# OurEDA-P1K_cam.net
KiCad netlist of a schematic drawn in Altium Designer
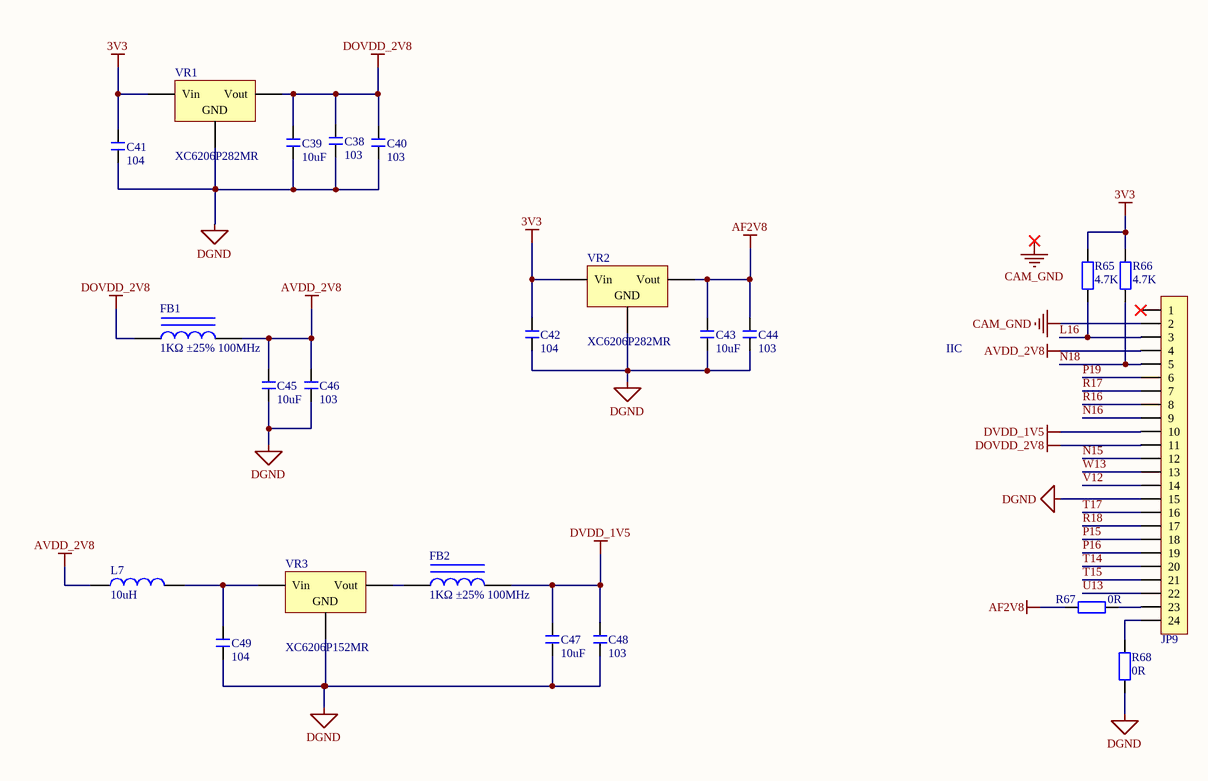
[diagram p0: OurEDA-P1K_cam.SchDoc]

(export (version "E")
  (design (tool "Eeschema 10.0.6"))
  (components
    (comp (ref "C38")
      (value "103")
      (footprint "C 0603_L")
      (description "无极性贴片电容")
      (fields (field (name "版权归属") "源创客"))
      (libsource (lib "3.1   - 电阻-电容-电感") (part "C"))
    )
    (comp (ref "C39")
      (value "10uF")
      (footprint "C 0603_L")
      (description "无极性贴片电容")
      (fields (field (name "版权归属") "源创客"))
      (libsource (lib "3.1   - 电阻-电容-电感") (part "C"))
    )
    (comp (ref "C40")
      (value "103")
      (footprint "C 0603_L")
      (description "无极性贴片电容")
      (fields (field (name "版权归属") "源创客"))
      (libsource (lib "3.1   - 电阻-电容-电感") (part "C"))
    )
    (comp (ref "C41")
      (value "104")
      (footprint "C 0603_L")
      (description "无极性贴片电容")
      (fields (field (name "版权归属") "源创客"))
      (libsource (lib "3.1   - 电阻-电容-电感") (part "C"))
    )
    (comp (ref "C42")
      (value "104")
      (footprint "C 0603_L")
      (description "无极性贴片电容")
      (fields (field (name "版权归属") "源创客"))
      (libsource (lib "3.1   - 电阻-电容-电感") (part "C"))
    )
    (comp (ref "C43")
      (value "10uF")
      (footprint "C 0603_L")
      (description "无极性贴片电容")
      (fields (field (name "版权归属") "源创客"))
      (libsource (lib "3.1   - 电阻-电容-电感") (part "C"))
    )
    (comp (ref "C44")
      (value "103")
      (footprint "C 0603_L")
      (description "无极性贴片电容")
      (fields (field (name "版权归属") "源创客"))
      (libsource (lib "3.1   - 电阻-电容-电感") (part "C"))
    )
    (comp (ref "C45")
      (value "10uF")
      (footprint "C 0603_L")
      (description "无极性贴片电容")
      (fields (field (name "版权归属") "源创客"))
      (libsource (lib "3.1   - 电阻-电容-电感") (part "C"))
    )
    (comp (ref "C46")
      (value "103")
      (footprint "C 0603_L")
      (description "无极性贴片电容")
      (fields (field (name "版权归属") "源创客"))
      (libsource (lib "3.1   - 电阻-电容-电感") (part "C"))
    )
    (comp (ref "C47")
      (value "10uF")
      (footprint "C 0603_L")
      (description "无极性贴片电容")
      (fields (field (name "版权归属") "源创客"))
      (libsource (lib "3.1   - 电阻-电容-电感") (part "C"))
    )
    (comp (ref "C48")
      (value "103")
      (footprint "C 0603_L")
      (description "无极性贴片电容")
      (fields (field (name "版权归属") "源创客"))
      (libsource (lib "3.1   - 电阻-电容-电感") (part "C"))
    )
    (comp (ref "C49")
      (value "104")
      (footprint "C 0603_L")
      (description "无极性贴片电容")
      (fields (field (name "版权归属") "源创客"))
      (libsource (lib "3.1   - 电阻-电容-电感") (part "C"))
    )
    (comp (ref "FB1")
      (value "1KΩ ±25% 100MHz")
      (footprint "0805_L")
      (description "贴片磁珠")
      (libsource (lib "Miscellaneous Devices LC") (part "0805 600Ω 25% 100MHz"))
    )
    (comp (ref "FB2")
      (value "1KΩ ±25% 100MHz")
      (footprint "0805_L")
      (description "贴片磁珠")
      (libsource (lib "Miscellaneous Devices LC") (part "0805 600Ω 25% 100MHz"))
    )
    (comp (ref "JP9")
      (value "FPC1.0-24P")
      (footprint "FPC0.5 2H-WS-24P")
      (description "FPC连接器")
      (fields (field (name "版权归属") "源创客"))
      (libsource (lib "4.14 - FPC连接器") (part "FPC-24P"))
    )
    (comp (ref "L7")
      (value "10uH")
      (footprint "L 0805")
      (description "小功率贴片电感")
      (fields (field (name "版权归属") "源创客"))
      (libsource (lib "3.1   - 电阻-电容-电感") (part "L"))
    )
    (comp (ref "R65")
      (value "4.7K")
      (footprint "R 0603_L")
      (description "贴片电阻")
      (fields (field (name "版权归属") "源创客"))
      (libsource (lib "3.1   - 电阻-电容-电感") (part "R"))
    )
    (comp (ref "R66")
      (value "4.7K")
      (footprint "R 0603_L")
      (description "贴片电阻")
      (fields (field (name "版权归属") "源创客"))
      (libsource (lib "3.1   - 电阻-电容-电感") (part "R"))
    )
    (comp (ref "R67")
      (value "0R")
      (footprint "R 0603_L")
      (description "贴片电阻")
      (fields (field (name "版权归属") "源创客"))
      (libsource (lib "3.1   - 电阻-电容-电感") (part "R"))
    )
    (comp (ref "R68")
      (value "0R")
      (footprint "R 0603_L")
      (description "贴片电阻")
      (fields (field (name "版权归属") "源创客"))
      (libsource (lib "3.1   - 电阻-电容-电感") (part "R"))
    )
    (comp (ref "VR1")
      (value "XC6206P282MR")
      (footprint "SOT-23-3L")
      (description "低压差线性稳压(LDO)")
      (libsource (lib "Miscellaneous Devices LC") (part "SOT-23 XC6206P332MR"))
    )
    (comp (ref "VR2")
      (value "XC6206P282MR")
      (footprint "SOT-23-3L")
      (description "低压差线性稳压(LDO)")
      (libsource (lib "Miscellaneous Devices LC") (part "SOT-23 XC6206P332MR"))
    )
    (comp (ref "VR3")
      (value "XC6206P152MR")
      (footprint "SOT-23-3L")
      (description "低压差线性稳压(LDO)")
      (libsource (lib "Miscellaneous Devices LC") (part "SOT-23 XC6206P332MR"))
    )
  )
  (nets
    (net (code "1") (name "/L16") (class "Default")
      (node (ref "JP9") (pin "3") (pinfunction "3_3") (pintype "passive"))
      (node (ref "R65") (pin "2") (pinfunction "2_2") (pintype "passive"))
    )
    (net (code "2") (name "/N15") (class "Default")
      (node (ref "JP9") (pin "12") (pinfunction "12_12") (pintype "passive"))
    )
    (net (code "3") (name "/N16") (class "Default")
      (node (ref "JP9") (pin "9") (pinfunction "9_9") (pintype "passive"))
    )
    (net (code "4") (name "/N18") (class "Default")
      (node (ref "JP9") (pin "5") (pinfunction "5_5") (pintype "passive"))
      (node (ref "R66") (pin "2") (pinfunction "2_2") (pintype "passive"))
    )
    (net (code "5") (name "/P15") (class "Default")
      (node (ref "JP9") (pin "18") (pinfunction "18_18") (pintype "passive"))
    )
    (net (code "6") (name "/P16") (class "Default")
      (node (ref "JP9") (pin "19") (pinfunction "19_19") (pintype "passive"))
    )
    (net (code "7") (name "/P19") (class "Default")
      (node (ref "JP9") (pin "6") (pinfunction "6_6") (pintype "passive"))
    )
    (net (code "8") (name "/R16") (class "Default")
      (node (ref "JP9") (pin "8") (pinfunction "8_8") (pintype "passive"))
    )
    (net (code "9") (name "/R17") (class "Default")
      (node (ref "JP9") (pin "7") (pinfunction "7_7") (pintype "passive"))
    )
    (net (code "10") (name "/R18") (class "Default")
      (node (ref "JP9") (pin "17") (pinfunction "17_17") (pintype "passive"))
    )
    (net (code "11") (name "/T14") (class "Default")
      (node (ref "JP9") (pin "20") (pinfunction "20_20") (pintype "passive"))
    )
    (net (code "12") (name "/T15") (class "Default")
      (node (ref "JP9") (pin "21") (pinfunction "21_21") (pintype "passive"))
    )
    (net (code "13") (name "/T17") (class "Default")
      (node (ref "JP9") (pin "16") (pinfunction "16_16") (pintype "passive"))
    )
    (net (code "14") (name "/U13") (class "Default")
      (node (ref "JP9") (pin "22") (pinfunction "22_22") (pintype "passive"))
    )
    (net (code "15") (name "/V12") (class "Default")
      (node (ref "JP9") (pin "14") (pinfunction "14_14") (pintype "passive"))
    )
    (net (code "16") (name "/W13") (class "Default")
      (node (ref "JP9") (pin "13") (pinfunction "13_13") (pintype "passive"))
    )
    (net (code "17") (name "3V3") (class "Default")
      (node (ref "C41") (pin "1") (pinfunction "1_1") (pintype "passive"))
      (node (ref "C42") (pin "1") (pinfunction "1_1") (pintype "passive"))
      (node (ref "R65") (pin "1") (pinfunction "1_1") (pintype "passive"))
      (node (ref "R66") (pin "1") (pinfunction "1_1") (pintype "passive"))
      (node (ref "VR1") (pin "3") (pinfunction "Vin_3") (pintype "passive"))
      (node (ref "VR2") (pin "3") (pinfunction "Vin_3") (pintype "passive"))
    )
    (net (code "18") (name "AF2V8") (class "Default")
      (node (ref "C43") (pin "1") (pinfunction "1_1") (pintype "passive"))
      (node (ref "C44") (pin "1") (pinfunction "1_1") (pintype "passive"))
      (node (ref "R67") (pin "1") (pinfunction "1_1") (pintype "passive"))
      (node (ref "VR2") (pin "2") (pinfunction "Vout_2") (pintype "passive"))
    )
    (net (code "19") (name "AVDD_2V8") (class "Default")
      (node (ref "C45") (pin "1") (pinfunction "1_1") (pintype "passive"))
      (node (ref "C46") (pin "1") (pinfunction "1_1") (pintype "passive"))
      (node (ref "FB1") (pin "2") (pinfunction "2_2") (pintype "passive"))
      (node (ref "JP9") (pin "4") (pinfunction "4_4") (pintype "passive"))
      (node (ref "L7") (pin "1") (pinfunction "1_1") (pintype "passive"))
    )
    (net (code "20") (name "CAM_GND") (class "Default")
      (node (ref "JP9") (pin "2") (pinfunction "2_2") (pintype "passive"))
    )
    (net (code "21") (name "DGND") (class "Default")
      (node (ref "C38") (pin "2") (pinfunction "2_2") (pintype "passive"))
      (node (ref "C39") (pin "2") (pinfunction "2_2") (pintype "passive"))
      (node (ref "C40") (pin "2") (pinfunction "2_2") (pintype "passive"))
      (node (ref "C41") (pin "2") (pinfunction "2_2") (pintype "passive"))
      (node (ref "C42") (pin "2") (pinfunction "2_2") (pintype "passive"))
      (node (ref "C43") (pin "2") (pinfunction "2_2") (pintype "passive"))
      (node (ref "C44") (pin "2") (pinfunction "2_2") (pintype "passive"))
      (node (ref "C45") (pin "2") (pinfunction "2_2") (pintype "passive"))
      (node (ref "C46") (pin "2") (pinfunction "2_2") (pintype "passive"))
      (node (ref "C47") (pin "2") (pinfunction "2_2") (pintype "passive"))
      (node (ref "C48") (pin "2") (pinfunction "2_2") (pintype "passive"))
      (node (ref "C49") (pin "2") (pinfunction "2_2") (pintype "passive"))
      (node (ref "JP9") (pin "15") (pinfunction "15_15") (pintype "passive"))
      (node (ref "R68") (pin "2") (pinfunction "2_2") (pintype "passive"))
      (node (ref "VR1") (pin "1") (pinfunction "GND_1") (pintype "passive"))
      (node (ref "VR2") (pin "1") (pinfunction "GND_1") (pintype "passive"))
      (node (ref "VR3") (pin "1") (pinfunction "GND_1") (pintype "passive"))
    )
    (net (code "22") (name "DOVDD_2V8") (class "Default")
      (node (ref "C38") (pin "1") (pinfunction "1_1") (pintype "passive"))
      (node (ref "C39") (pin "1") (pinfunction "1_1") (pintype "passive"))
      (node (ref "C40") (pin "1") (pinfunction "1_1") (pintype "passive"))
      (node (ref "FB1") (pin "1") (pinfunction "1_1") (pintype "passive"))
      (node (ref "JP9") (pin "11") (pinfunction "11_11") (pintype "passive"))
      (node (ref "VR1") (pin "2") (pinfunction "Vout_2") (pintype "passive"))
    )
    (net (code "23") (name "DVDD_1V5") (class "Default")
      (node (ref "C47") (pin "1") (pinfunction "1_1") (pintype "passive"))
      (node (ref "C48") (pin "1") (pinfunction "1_1") (pintype "passive"))
      (node (ref "FB2") (pin "2") (pinfunction "2_2") (pintype "passive"))
      (node (ref "JP9") (pin "10") (pinfunction "10_10") (pintype "passive"))
    )
    (net (code "24") (name "Net-(JP9-Pad23)") (class "Default")
      (node (ref "JP9") (pin "23") (pinfunction "23_23") (pintype "passive"))
      (node (ref "R67") (pin "2") (pinfunction "2_2") (pintype "passive"))
    )
    (net (code "25") (name "Net-(JP9-Pad24)") (class "Default")
      (node (ref "JP9") (pin "24") (pinfunction "24_24") (pintype "passive"))
      (node (ref "R68") (pin "1") (pinfunction "1_1") (pintype "passive"))
    )
    (net (code "26") (name "Net-(VR3-Vin)") (class "Default")
      (node (ref "C49") (pin "1") (pinfunction "1_1") (pintype "passive"))
      (node (ref "L7") (pin "2") (pinfunction "2_2") (pintype "passive"))
      (node (ref "VR3") (pin "3") (pinfunction "Vin_3") (pintype "passive"))
    )
    (net (code "27") (name "Net-(VR3-Vout)") (class "Default")
      (node (ref "FB2") (pin "1") (pinfunction "1_1") (pintype "passive"))
      (node (ref "VR3") (pin "2") (pinfunction "Vout_2") (pintype "passive"))
    )
    (net (code "28") (name "unconnected-(JP9-Pad1)") (class "Default")
      (node (ref "JP9") (pin "1") (pinfunction "1_1") (pintype "passive+no_connect"))
    )
  )
)
